# LB_BIT_i35_delay-v03_5_5.net
KiCad netlist of a schematic drawn in EAGLE
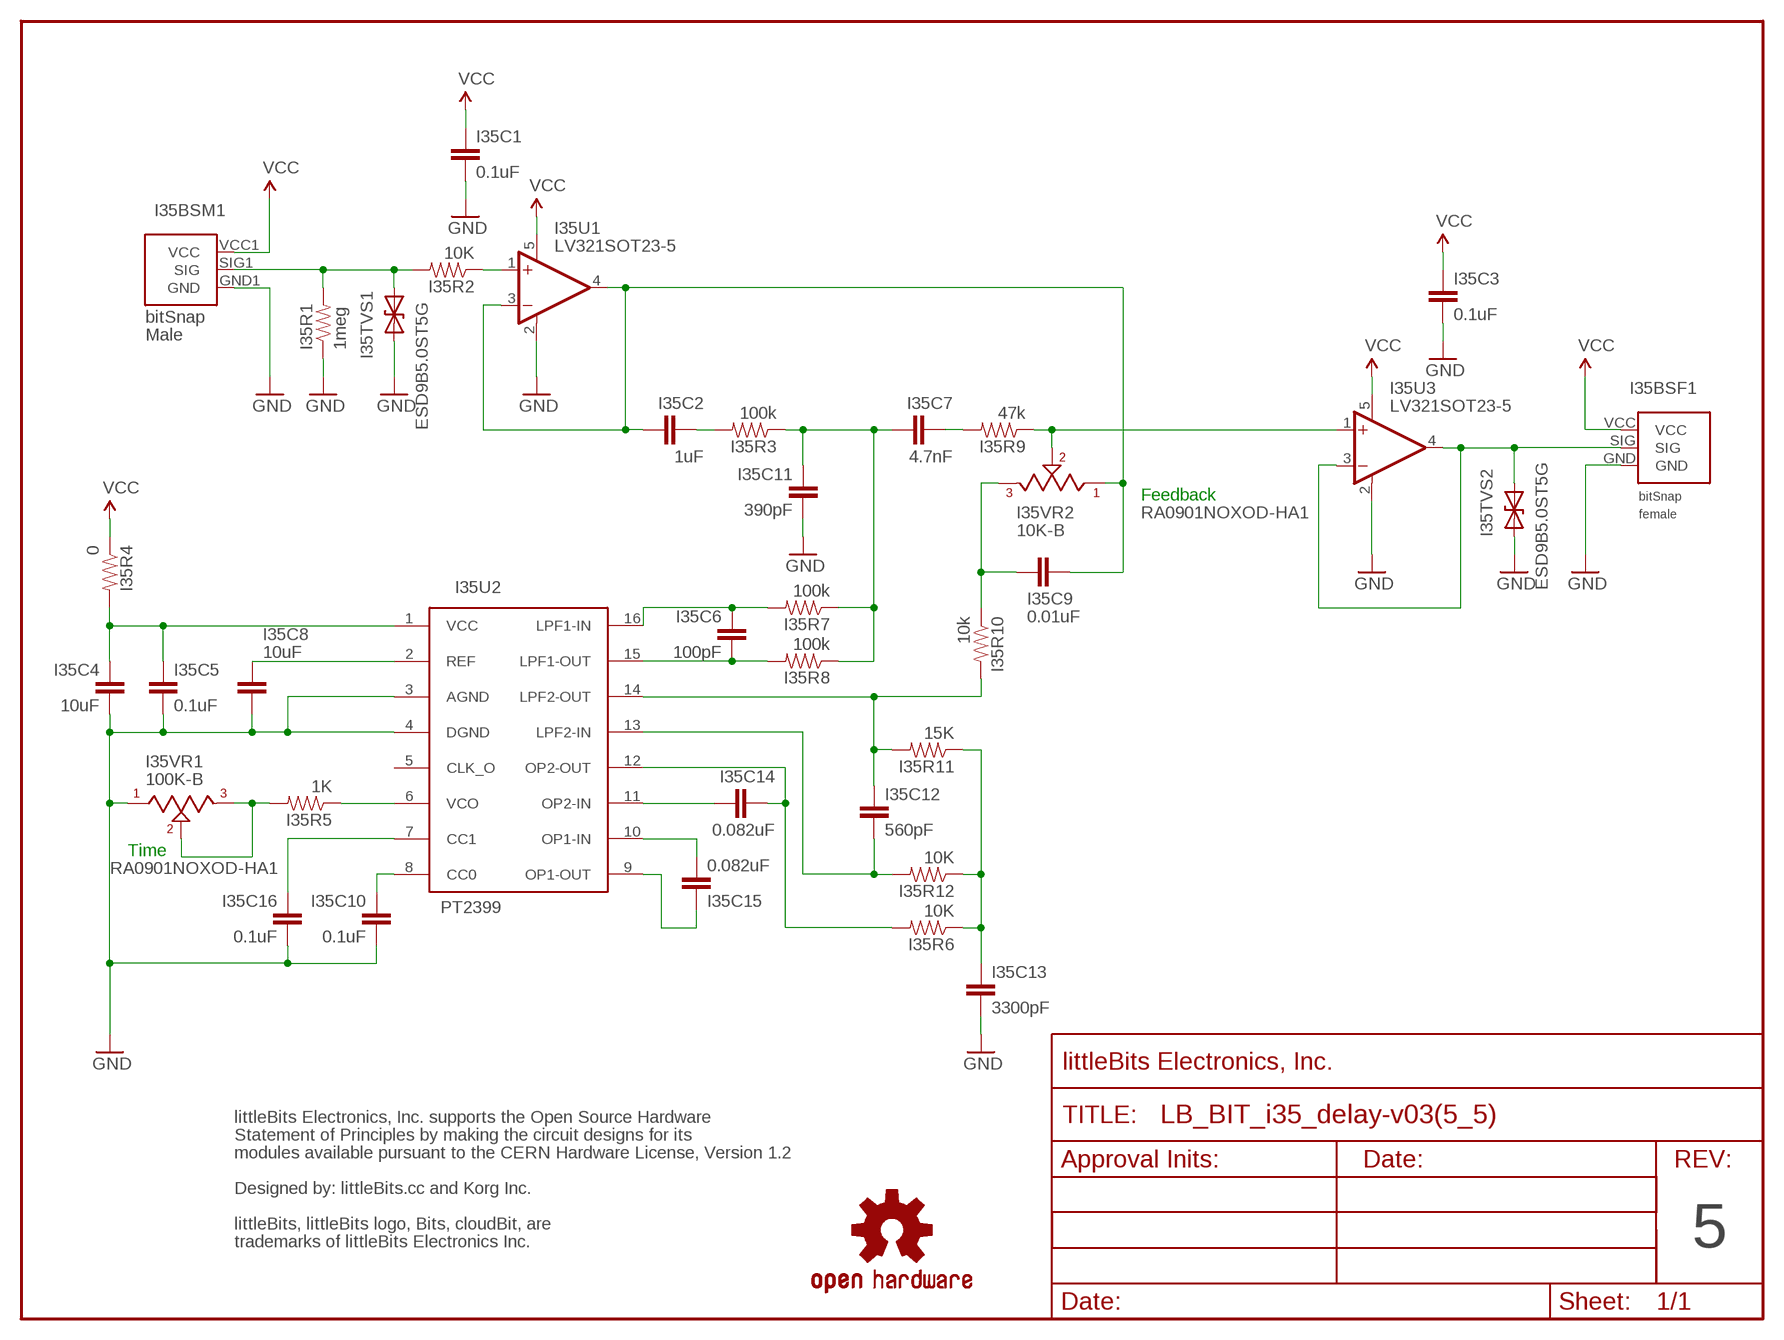
[diagram p0: schematic, sheet 1]

(export (version "E")
  (design (tool "Eeschema 10.0.6"))
  (components
    (comp (ref "I35BSF1")
      (value "BITSNAP_V03_FEMALE")
      (footprint "eagle-import:BITSNAP_V03_FEMALE")
      (libsource (lib "eagle-import") (part "BITSNAP_V03_FEMALE"))
    )
    (comp (ref "I35BSM1")
      (value "BITSNAP_V03_MALE")
      (footprint "eagle-import:BITSNAP_V03_MALE")
      (libsource (lib "eagle-import") (part "BITSNAP_V03_MALE"))
    )
    (comp (ref "I35C1")
      (value "0.1uF")
      (footprint "eagle-import:CAP-0603")
      (libsource (lib "eagle-import") (part "CAPCAP-0603"))
    )
    (comp (ref "I35C2")
      (value "1uF")
      (footprint "eagle-import:CAP-0603")
      (libsource (lib "eagle-import") (part "CAPCAP-0603"))
    )
    (comp (ref "I35C3")
      (value "0.1uF")
      (footprint "eagle-import:CAP-0603")
      (libsource (lib "eagle-import") (part "CAPCAP-0603"))
    )
    (comp (ref "I35C4")
      (value "10uF")
      (footprint "eagle-import:CAP-0603")
      (libsource (lib "eagle-import") (part "CAPCAP-0603"))
    )
    (comp (ref "I35C5")
      (value "0.1uF")
      (footprint "eagle-import:CAP-0603")
      (libsource (lib "eagle-import") (part "CAPCAP-0603"))
    )
    (comp (ref "I35C6")
      (value "100pF")
      (footprint "eagle-import:CAP-0603")
      (libsource (lib "eagle-import") (part "CAPCAP-0603"))
    )
    (comp (ref "I35C7")
      (value "4.7nF")
      (footprint "eagle-import:CAP-0603")
      (libsource (lib "eagle-import") (part "CAPCAP-0603"))
    )
    (comp (ref "I35C8")
      (value "10uF")
      (footprint "eagle-import:CAP-0603")
      (libsource (lib "eagle-import") (part "CAPCAP-0603"))
    )
    (comp (ref "I35C9")
      (value "0.01uF")
      (footprint "eagle-import:CAP-0603")
      (libsource (lib "eagle-import") (part "CAPCAP-0603"))
    )
    (comp (ref "I35C10")
      (value "0.1uF")
      (footprint "eagle-import:CAP-0603")
      (libsource (lib "eagle-import") (part "CAPCAP-0603"))
    )
    (comp (ref "I35C11")
      (value "390pF")
      (footprint "eagle-import:CAP-0603")
      (libsource (lib "eagle-import") (part "CAPCAP-0603"))
    )
    (comp (ref "I35C12")
      (value "560pF")
      (footprint "eagle-import:CAP-0603")
      (libsource (lib "eagle-import") (part "CAPCAP-0603"))
    )
    (comp (ref "I35C13")
      (value "3300pF")
      (footprint "eagle-import:CAP-0603")
      (libsource (lib "eagle-import") (part "CAPCAP-0603"))
    )
    (comp (ref "I35C14")
      (value "0.082uF")
      (footprint "eagle-import:CAP-0603")
      (libsource (lib "eagle-import") (part "CAPCAP-0603"))
    )
    (comp (ref "I35C15")
      (value "0.082uF")
      (footprint "eagle-import:CAP-0603")
      (libsource (lib "eagle-import") (part "CAPCAP-0603"))
    )
    (comp (ref "I35C16")
      (value "0.1uF")
      (footprint "eagle-import:CAP-0603")
      (libsource (lib "eagle-import") (part "CAPCAP-0603"))
    )
    (comp (ref "I35R1")
      (value "1meg")
      (footprint "eagle-import:RES-0603")
      (libsource (lib "eagle-import") (part "RESISTOR0603"))
    )
    (comp (ref "I35R2")
      (value "10K")
      (footprint "eagle-import:RES-0603")
      (libsource (lib "eagle-import") (part "RESISTOR0603"))
    )
    (comp (ref "I35R3")
      (value "100k")
      (footprint "eagle-import:RES-0603")
      (libsource (lib "eagle-import") (part "RESISTOR0603"))
    )
    (comp (ref "I35R4")
      (value "0")
      (footprint "eagle-import:RES-0603")
      (libsource (lib "eagle-import") (part "RESISTOR0603"))
    )
    (comp (ref "I35R5")
      (value "1K")
      (footprint "eagle-import:RES-0603")
      (libsource (lib "eagle-import") (part "RESISTOR0603"))
    )
    (comp (ref "I35R6")
      (value "10K")
      (footprint "eagle-import:RES-0603")
      (libsource (lib "eagle-import") (part "RESISTOR0603"))
    )
    (comp (ref "I35R7")
      (value "100k")
      (footprint "eagle-import:RES-0603")
      (libsource (lib "eagle-import") (part "RESISTOR0603"))
    )
    (comp (ref "I35R8")
      (value "100k")
      (footprint "eagle-import:RES-0603")
      (libsource (lib "eagle-import") (part "RESISTOR0603"))
    )
    (comp (ref "I35R9")
      (value "47k")
      (footprint "eagle-import:RES-0603")
      (libsource (lib "eagle-import") (part "RESISTOR0603"))
    )
    (comp (ref "I35R10")
      (value "10k")
      (footprint "eagle-import:RES-0603")
      (libsource (lib "eagle-import") (part "RESISTOR0603"))
    )
    (comp (ref "I35R11")
      (value "15K")
      (footprint "eagle-import:RES-0603")
      (libsource (lib "eagle-import") (part "RESISTOR0603"))
    )
    (comp (ref "I35R12")
      (value "10K")
      (footprint "eagle-import:RES-0603")
      (libsource (lib "eagle-import") (part "RESISTOR0603"))
    )
    (comp (ref "I35TVS1")
      (value "ESD9B5.0ST5G")
      (footprint "eagle-import:SOD-923")
      (libsource (lib "eagle-import") (part "DIODE-TVSSOD-923"))
    )
    (comp (ref "I35TVS2")
      (value "ESD9B5.0ST5G")
      (footprint "eagle-import:SOD-923")
      (libsource (lib "eagle-import") (part "DIODE-TVSSOD-923"))
    )
    (comp (ref "I35U1")
      (value "LV321SOT23-5")
      (footprint "eagle-import:SOT23-5")
      (libsource (lib "eagle-import") (part "LV321SOT23-5"))
    )
    (comp (ref "I35U2")
      (value "PT2399")
      (footprint "eagle-import:SO16")
      (libsource (lib "eagle-import") (part "PT2399"))
    )
    (comp (ref "I35U3")
      (value "LV321SOT23-5")
      (footprint "eagle-import:SOT23-5")
      (libsource (lib "eagle-import") (part "LV321SOT23-5"))
    )
    (comp (ref "I35VR1")
      (value "100K-B")
      (footprint "eagle-import:ALPS_POT")
      (libsource (lib "eagle-import") (part "ALPS_POTTH"))
    )
    (comp (ref "I35VR2")
      (value "10K-B")
      (footprint "eagle-import:ALPS_POT")
      (libsource (lib "eagle-import") (part "ALPS_POTTH"))
    )
    (comp (ref "U$1")
      (value "FRAME-LETTER-OHWOHW")
      (footprint "eagle-import:FABDWG01-OHW")
      (libsource (lib "eagle-import") (part "FRAME-LETTER-OHWOHW"))
    )
    (comp (ref "U$2")
      (value "OSHWCREDIT-KORG")
      (footprint "eagle-import:OSHWCREDIT-KORG")
      (libsource (lib "eagle-import") (part "OSHWCREDIT-KORG"))
    )
    (comp (ref "U$3")
      (value "OSHW-LOGOL")
      (footprint "eagle-import:OSHW-LOGO-L")
      (libsource (lib "eagle-import") (part "OSHW-LOGOL"))
    )
  )
  (nets
    (net (code "1") (name "GND") (class "Default")
      (node (ref "I35BSF1") (pin "GND") (pinfunction "GND_GND") (pintype "bidirectional"))
      (node (ref "I35BSM1") (pin "GND1") (pinfunction "GND_GND1") (pintype "bidirectional"))
      (node (ref "I35C1") (pin "2") (pinfunction "2_2") (pintype "passive"))
      (node (ref "I35C10") (pin "2") (pinfunction "2_2") (pintype "passive"))
      (node (ref "I35C11") (pin "2") (pinfunction "2_2") (pintype "passive"))
      (node (ref "I35C13") (pin "2") (pinfunction "2_2") (pintype "passive"))
      (node (ref "I35C16") (pin "2") (pinfunction "2_2") (pintype "passive"))
      (node (ref "I35C3") (pin "2") (pinfunction "2_2") (pintype "passive"))
      (node (ref "I35C4") (pin "2") (pinfunction "2_2") (pintype "passive"))
      (node (ref "I35C5") (pin "2") (pinfunction "2_2") (pintype "passive"))
      (node (ref "I35C8") (pin "2") (pinfunction "2_2") (pintype "passive"))
      (node (ref "I35R1") (pin "1") (pinfunction "1_1") (pintype "passive"))
      (node (ref "I35TVS1") (pin "1") (pinfunction "A_1") (pintype "passive"))
      (node (ref "I35TVS2") (pin "1") (pinfunction "A_1") (pintype "passive"))
      (node (ref "I35U1") (pin "2") (pinfunction "V-_2") (pintype "power_in"))
      (node (ref "I35U2") (pin "3") (pinfunction "AGND_3") (pintype "power_in"))
      (node (ref "I35U2") (pin "4") (pinfunction "DGND_4") (pintype "power_in"))
      (node (ref "I35U3") (pin "2") (pinfunction "V-_2") (pintype "power_in"))
      (node (ref "I35VR1") (pin "1") (pinfunction "1_1") (pintype "passive"))
    )
    (net (code "2") (name "Net-(I35BSM1-SIG)") (class "Default")
      (node (ref "I35BSM1") (pin "SIG1") (pinfunction "SIG_SIG1") (pintype "bidirectional"))
      (node (ref "I35R1") (pin "2") (pinfunction "2_2") (pintype "passive"))
      (node (ref "I35R2") (pin "2") (pinfunction "2_2") (pintype "passive"))
      (node (ref "I35TVS1") (pin "2") (pinfunction "C_2") (pintype "passive"))
    )
    (net (code "3") (name "Net-(I35C2-Pad2)") (class "Default")
      (node (ref "I35C2") (pin "2") (pinfunction "2_2") (pintype "passive"))
      (node (ref "I35R3") (pin "2") (pinfunction "2_2") (pintype "passive"))
    )
    (net (code "4") (name "Net-(I35C7-Pad2)") (class "Default")
      (node (ref "I35C7") (pin "2") (pinfunction "2_2") (pintype "passive"))
      (node (ref "I35R9") (pin "2") (pinfunction "2_2") (pintype "passive"))
    )
    (net (code "5") (name "Net-(I35C9-Pad1)") (class "Default")
      (node (ref "I35C9") (pin "1") (pinfunction "1_1") (pintype "passive"))
      (node (ref "I35R10") (pin "1") (pinfunction "1_1") (pintype "passive"))
      (node (ref "I35VR2") (pin "3") (pinfunction "3_3") (pintype "passive"))
    )
    (net (code "6") (name "Net-(I35C11-Pad1)") (class "Default")
      (node (ref "I35C11") (pin "1") (pinfunction "1_1") (pintype "passive"))
      (node (ref "I35C7") (pin "1") (pinfunction "1_1") (pintype "passive"))
      (node (ref "I35R3") (pin "1") (pinfunction "1_1") (pintype "passive"))
      (node (ref "I35R7") (pin "1") (pinfunction "1_1") (pintype "passive"))
      (node (ref "I35R8") (pin "1") (pinfunction "1_1") (pintype "passive"))
    )
    (net (code "7") (name "Net-(I35C13-Pad1)") (class "Default")
      (node (ref "I35C13") (pin "1") (pinfunction "1_1") (pintype "passive"))
      (node (ref "I35R11") (pin "1") (pinfunction "1_1") (pintype "passive"))
      (node (ref "I35R12") (pin "1") (pinfunction "1_1") (pintype "passive"))
      (node (ref "I35R6") (pin "1") (pinfunction "1_1") (pintype "passive"))
    )
    (net (code "8") (name "Net-(I35R5-Pad2)") (class "Default")
      (node (ref "I35R5") (pin "2") (pinfunction "2_2") (pintype "passive"))
      (node (ref "I35VR1") (pin "2") (pinfunction "2_2") (pintype "passive"))
      (node (ref "I35VR1") (pin "3") (pinfunction "3_3") (pintype "passive"))
    )
    (net (code "9") (name "Net-(I35TVS2-C)") (class "Default")
      (node (ref "I35BSF1") (pin "SIG") (pinfunction "SIG_SIG") (pintype "bidirectional"))
      (node (ref "I35TVS2") (pin "2") (pinfunction "C_2") (pintype "passive"))
      (node (ref "I35U3") (pin "3") (pinfunction "-IN_3") (pintype "input"))
      (node (ref "I35U3") (pin "4") (pinfunction "OUT_4") (pintype "output"))
    )
    (net (code "10") (name "Net-(I35U1-+IN)") (class "Default")
      (node (ref "I35R2") (pin "1") (pinfunction "1_1") (pintype "passive"))
      (node (ref "I35U1") (pin "1") (pinfunction "+IN_1") (pintype "input"))
    )
    (net (code "11") (name "Net-(I35U1--IN)") (class "Default")
      (node (ref "I35C2") (pin "1") (pinfunction "1_1") (pintype "passive"))
      (node (ref "I35C9") (pin "2") (pinfunction "2_2") (pintype "passive"))
      (node (ref "I35U1") (pin "3") (pinfunction "-IN_3") (pintype "input"))
      (node (ref "I35U1") (pin "4") (pinfunction "OUT_4") (pintype "output"))
      (node (ref "I35VR2") (pin "1") (pinfunction "1_1") (pintype "passive"))
    )
    (net (code "12") (name "Net-(I35U2-CC0)") (class "Default")
      (node (ref "I35C10") (pin "1") (pinfunction "1_1") (pintype "passive"))
      (node (ref "I35U2") (pin "8") (pinfunction "CC0_8") (pintype "bidirectional"))
    )
    (net (code "13") (name "Net-(I35U2-CC1)") (class "Default")
      (node (ref "I35C16") (pin "1") (pinfunction "1_1") (pintype "passive"))
      (node (ref "I35U2") (pin "7") (pinfunction "CC1_7") (pintype "bidirectional"))
    )
    (net (code "14") (name "Net-(I35U2-LPF1-IN)") (class "Default")
      (node (ref "I35C6") (pin "1") (pinfunction "1_1") (pintype "passive"))
      (node (ref "I35R7") (pin "2") (pinfunction "2_2") (pintype "passive"))
      (node (ref "I35U2") (pin "16") (pinfunction "LPF1-IN_16") (pintype "bidirectional"))
    )
    (net (code "15") (name "Net-(I35U2-LPF1-OUT)") (class "Default")
      (node (ref "I35C6") (pin "2") (pinfunction "2_2") (pintype "passive"))
      (node (ref "I35R8") (pin "2") (pinfunction "2_2") (pintype "passive"))
      (node (ref "I35U2") (pin "15") (pinfunction "LPF1-OUT_15") (pintype "bidirectional"))
    )
    (net (code "16") (name "Net-(I35U2-LPF2-IN)") (class "Default")
      (node (ref "I35C12") (pin "2") (pinfunction "2_2") (pintype "passive"))
      (node (ref "I35R12") (pin "2") (pinfunction "2_2") (pintype "passive"))
      (node (ref "I35U2") (pin "13") (pinfunction "LPF2-IN_13") (pintype "bidirectional"))
    )
    (net (code "17") (name "Net-(I35U2-LPF2-OUT)") (class "Default")
      (node (ref "I35C12") (pin "1") (pinfunction "1_1") (pintype "passive"))
      (node (ref "I35R10") (pin "2") (pinfunction "2_2") (pintype "passive"))
      (node (ref "I35R11") (pin "2") (pinfunction "2_2") (pintype "passive"))
      (node (ref "I35U2") (pin "14") (pinfunction "LPF2-OUT_14") (pintype "bidirectional"))
    )
    (net (code "18") (name "Net-(I35U2-OP1-IN)") (class "Default")
      (node (ref "I35C15") (pin "2") (pinfunction "2_2") (pintype "passive"))
      (node (ref "I35U2") (pin "10") (pinfunction "OP1-IN_10") (pintype "bidirectional"))
    )
    (net (code "19") (name "Net-(I35U2-OP1-OUT)") (class "Default")
      (node (ref "I35C15") (pin "1") (pinfunction "1_1") (pintype "passive"))
      (node (ref "I35U2") (pin "9") (pinfunction "OP1-OUT_9") (pintype "bidirectional"))
    )
    (net (code "20") (name "Net-(I35U2-OP2-IN)") (class "Default")
      (node (ref "I35C14") (pin "1") (pinfunction "1_1") (pintype "passive"))
      (node (ref "I35U2") (pin "11") (pinfunction "OP2-IN_11") (pintype "bidirectional"))
    )
    (net (code "21") (name "Net-(I35U2-OP2-OUT)") (class "Default")
      (node (ref "I35C14") (pin "2") (pinfunction "2_2") (pintype "passive"))
      (node (ref "I35R6") (pin "2") (pinfunction "2_2") (pintype "passive"))
      (node (ref "I35U2") (pin "12") (pinfunction "OP2-OUT_12") (pintype "bidirectional"))
    )
    (net (code "22") (name "Net-(I35U2-REF)") (class "Default")
      (node (ref "I35C8") (pin "1") (pinfunction "1_1") (pintype "passive"))
      (node (ref "I35U2") (pin "2") (pinfunction "REF_2") (pintype "bidirectional"))
    )
    (net (code "23") (name "Net-(I35U2-VCC)") (class "Default")
      (node (ref "I35C4") (pin "1") (pinfunction "1_1") (pintype "passive"))
      (node (ref "I35C5") (pin "1") (pinfunction "1_1") (pintype "passive"))
      (node (ref "I35R4") (pin "2") (pinfunction "2_2") (pintype "passive"))
      (node (ref "I35U2") (pin "1") (pinfunction "VCC_1") (pintype "power_in"))
    )
    (net (code "24") (name "Net-(I35U2-VCO)") (class "Default")
      (node (ref "I35R5") (pin "1") (pinfunction "1_1") (pintype "passive"))
      (node (ref "I35U2") (pin "6") (pinfunction "VCO_6") (pintype "bidirectional"))
    )
    (net (code "25") (name "Net-(I35U3-+IN)") (class "Default")
      (node (ref "I35R9") (pin "1") (pinfunction "1_1") (pintype "passive"))
      (node (ref "I35U3") (pin "1") (pinfunction "+IN_1") (pintype "input"))
      (node (ref "I35VR2") (pin "2") (pinfunction "2_2") (pintype "passive"))
    )
    (net (code "26") (name "VCC") (class "Default")
      (node (ref "I35BSF1") (pin "VCC") (pinfunction "VCC_VCC") (pintype "bidirectional"))
      (node (ref "I35BSM1") (pin "VCC1") (pinfunction "VCC_VCC1") (pintype "bidirectional"))
      (node (ref "I35C1") (pin "1") (pinfunction "1_1") (pintype "passive"))
      (node (ref "I35C3") (pin "1") (pinfunction "1_1") (pintype "passive"))
      (node (ref "I35R4") (pin "1") (pinfunction "1_1") (pintype "passive"))
      (node (ref "I35U1") (pin "5") (pinfunction "V+_5") (pintype "power_in"))
      (node (ref "I35U3") (pin "5") (pinfunction "V+_5") (pintype "power_in"))
    )
    (net (code "27") (name "unconnected-(I35U2-CLK_O-Pad5)") (class "Default")
      (node (ref "I35U2") (pin "5") (pinfunction "CLK_O_5") (pintype "bidirectional"))
    )
  )
)
